# tia.net
KiCad netlist of a schematic drawn in Altium Designer
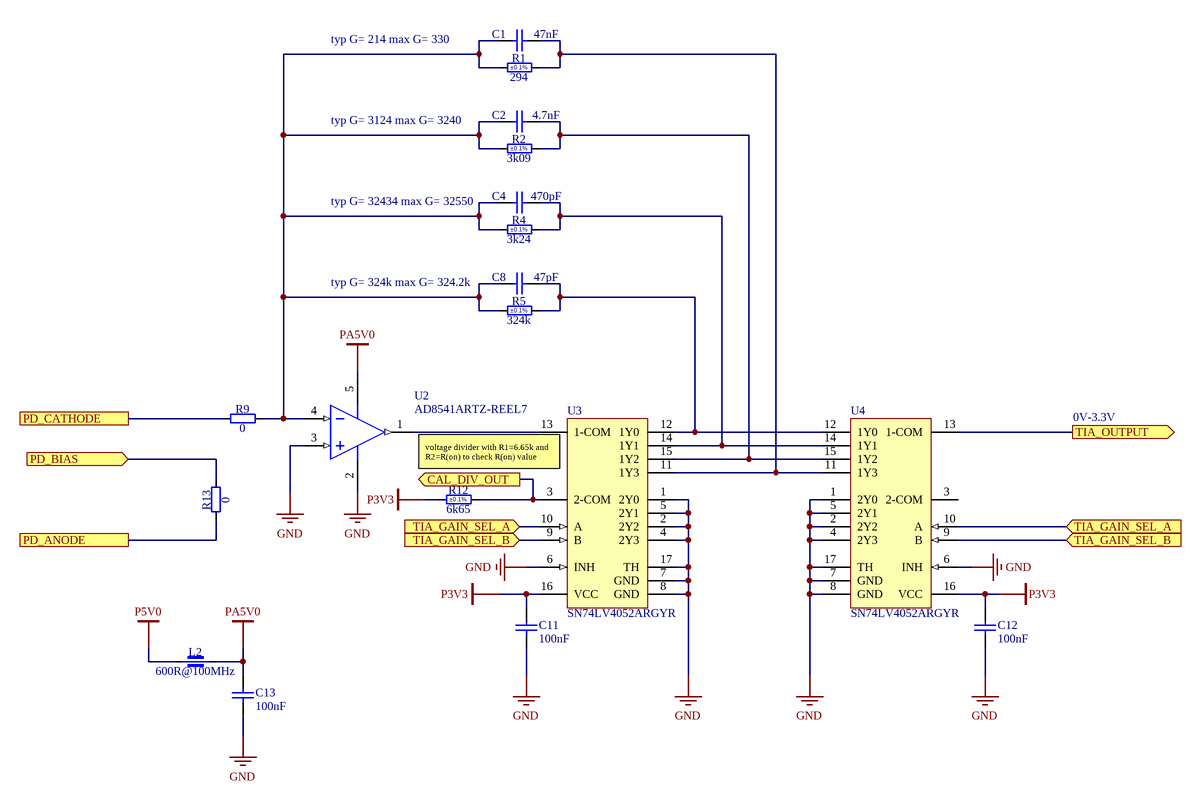
[diagram p0: tia.SchDoc]

(export (version "E")
  (design (tool "Eeschema 10.0.6"))
  (components
    (comp (ref "C1")
      (value "47nF")
      (footprint "CAPC1005X55N")
      (description "Non-polarised capacitor")
      (fields
        (field (name "PART NUMBER") "CC0402_47NF_16V_10%_X7R")
        (field (name "VOLTAGE") "16V")
        (field (name "AUTHOR") "CERN DEM JLC")
      )
      (libsource (lib "Capacitors") (part "Capacitor - non polarized"))
    )
    (comp (ref "C2")
      (value "4.7nF")
      (footprint "CAPC1005X55N")
      (description "Non-polarised capacitor")
      (fields
        (field (name "PART NUMBER") "CC0402_4.7NF_16V_10%_X7R")
        (field (name "VOLTAGE") "16V")
        (field (name "AUTHOR") "CERN DEM JLC")
      )
      (libsource (lib "Capacitors") (part "Capacitor - non polarized"))
    )
    (comp (ref "C4")
      (value "470pF")
      (footprint "CAPC1005X55N")
      (description "Non-polarised capacitor")
      (fields
        (field (name "PART NUMBER") "CC0402_470PF_50V_10%_X7R")
        (field (name "VOLTAGE") "50V")
        (field (name "AUTHOR") "CERN DEM JLC")
      )
      (libsource (lib "Capacitors") (part "Capacitor - non polarized"))
    )
    (comp (ref "C8")
      (value "47pF")
      (footprint "CAPC1005X55N")
      (description "Non-polarised capacitor")
      (fields
        (field (name "PART NUMBER") "CC0402_47PF_50V_5%_C0G")
        (field (name "VOLTAGE") "50V")
        (field (name "AUTHOR") "CERN DEM JLC")
      )
      (libsource (lib "Capacitors") (part "Capacitor - non polarized"))
    )
    (comp (ref "C11")
      (value "100nF")
      (footprint "CAPC1005X55N")
      (description "Non-polarised capacitor")
      (fields
        (field (name "TOLERANCE") "±10%")
        (field (name "VOLTAGE") "16V")
        (field (name "AUTHOR") "CERN DEM JLC")
      )
      (libsource (lib "Capacitors") (part "Capacitor - non polarized"))
    )
    (comp (ref "C12")
      (value "100nF")
      (footprint "CAPC1005X55N")
      (description "Non-polarised capacitor")
      (fields
        (field (name "TOLERANCE") "±10%")
        (field (name "VOLTAGE") "16V")
        (field (name "AUTHOR") "CERN DEM JLC")
      )
      (libsource (lib "Capacitors") (part "Capacitor - non polarized"))
    )
    (comp (ref "C13")
      (value "100nF")
      (footprint "CAPC1005X55N")
      (description "Non-polarised capacitor")
      (fields
        (field (name "TOLERANCE") "±10%")
        (field (name "VOLTAGE") "16V")
        (field (name "AUTHOR") "CERN DEM JLC")
      )
      (libsource (lib "Capacitors") (part "Capacitor - non polarized"))
    )
    (comp (ref "L2")
      (value "600R@100MHz")
      (footprint "INDC1005X55N")
      (fields
        (field (name "PART NUMBER") "IND0402_MURATA_BLM15HD601SN1")
        (field (name "POWER") "300mA")
        (field (name "TOLERANCE") "±25%")
        (field (name "AUTHOR") "CERN DEM JLC")
      )
      (libsource (lib "Inductors & Transformers") (part "Ferrite Bead"))
    )
    (comp (ref "R1")
      (value "294")
      (footprint "RESC1005X40N")
      (description "Resistor - 1%")
      (fields
        (field (name "TOLERANCE") "±0.1%")
        (field (name "PART NUMBER") "R0402_10K_1%_0.0625W_100PPM")
        (field (name "POWER") "0.0625W")
        (field (name "AUTHOR") "CERN DEM JLC")
      )
      (libsource (lib "Resistors") (part "Resistor - 1%"))
    )
    (comp (ref "R2")
      (value "3k09")
      (footprint "RESC1005X40N")
      (description "Resistor - 1%")
      (fields
        (field (name "TOLERANCE") "±0.1%")
        (field (name "PART NUMBER") "R0402_10K_1%_0.0625W_100PPM")
        (field (name "POWER") "0.0625W")
        (field (name "AUTHOR") "CERN DEM JLC")
      )
      (libsource (lib "Resistors") (part "Resistor - 1%"))
    )
    (comp (ref "R4")
      (value "3k24")
      (footprint "RESC1005X40N")
      (description "Resistor - 1%")
      (fields
        (field (name "TOLERANCE") "±0.1%")
        (field (name "PART NUMBER") "R0402_10K_1%_0.0625W_100PPM")
        (field (name "POWER") "0.0625W")
        (field (name "AUTHOR") "CERN DEM JLC")
      )
      (libsource (lib "Resistors") (part "Resistor - 1%"))
    )
    (comp (ref "R5")
      (value "324k")
      (footprint "RESC1005X40N")
      (description "Resistor - 1%")
      (fields
        (field (name "TOLERANCE") "±0.1%")
        (field (name "PART NUMBER") "R0402_10K_1%_0.0625W_100PPM")
        (field (name "POWER") "0.0625W")
        (field (name "AUTHOR") "CERN DEM JLC")
      )
      (libsource (lib "Resistors") (part "Resistor - 1%"))
    )
    (comp (ref "R9")
      (value "0")
      (footprint "RESC1005X40N")
      (description "Resistor")
      (fields
        (field (name "PART NUMBER") "R0402_0R_JUMPER")
        (field (name "MANUFACTURER") "GENERIC")
        (field (name "AUTHOR") "CERN DEM JLC")
      )
      (libsource (lib "Resistors") (part "Resistor"))
    )
    (comp (ref "R12")
      (value "6k65")
      (footprint "RESC1005X40N")
      (description "Resistor - 1%")
      (fields
        (field (name "TOLERANCE") "±0.1%")
        (field (name "PART NUMBER") "R0402_10K_1%_0.0625W_100PPM")
        (field (name "POWER") "0.0625W")
        (field (name "AUTHOR") "CERN DEM JLC")
      )
      (libsource (lib "Resistors") (part "Resistor - 1%"))
    )
    (comp (ref "R13")
      (value "0")
      (footprint "RESC1005X40N")
      (description "Resistor")
      (fields
        (field (name "PART NUMBER") "R0402_0R_JUMPER")
        (field (name "MANUFACTURER") "GENERIC")
        (field (name "AUTHOR") "CERN DEM JLC")
      )
      (libsource (lib "Resistors") (part "Resistor"))
    )
    (comp (ref "U2")
      (value "AD8541ARTZ-REEL7")
      (footprint "ADI-RJ-5_N")
      (fields (field (name "MANUFACTURER") "Analog Devices") (field (name "GENERIC PART NUMBER") "AD8541"))
      (libsource (lib "Altium Content Vault") (part "ADI-AD85XX-5"))
    )
    (comp (ref "U3")
      (value "SN74LV4052ARGYR")
      (footprint "FP-RGY0016A-MFG")
      (description "IC MULTIPLEXER DUAL 4X1 16VQFN")
      (libsource (lib "DiPho") (part "SN74LV4052ARGYR"))
    )
    (comp (ref "U4")
      (value "SN74LV4052ARGYR")
      (footprint "FP-RGY0016A-MFG")
      (description "IC MULTIPLEXER DUAL 4X1 16VQFN")
      (libsource (lib "") (part "SN74LV4052ARGYR_1"))
    )
  )
  (nets
    (net (code "1") (name "/CAL_DIV_OUT") (class "Default")
      (node (ref "R12") (pin "2") (pinfunction "2_2") (pintype "passive"))
      (node (ref "U3") (pin "3") (pinfunction "2-COM_3") (pintype "passive"))
    )
    (net (code "2") (name "/PD_ANODE") (class "Default")
      (node (ref "R13") (pin "1") (pinfunction "1_1") (pintype "passive"))
    )
    (net (code "3") (name "/PD_BIAS") (class "Default")
      (node (ref "R13") (pin "2") (pinfunction "2_2") (pintype "passive"))
    )
    (net (code "4") (name "/PD_CATHODE") (class "Default")
      (node (ref "R9") (pin "1") (pinfunction "1_1") (pintype "passive"))
    )
    (net (code "5") (name "/TIA_GAIN_SEL_A") (class "Default")
      (node (ref "U3") (pin "10") (pinfunction "A_10") (pintype "input"))
      (node (ref "U4") (pin "10") (pinfunction "A_10") (pintype "input"))
    )
    (net (code "6") (name "/TIA_GAIN_SEL_B") (class "Default")
      (node (ref "U3") (pin "9") (pinfunction "B_9") (pintype "input"))
      (node (ref "U4") (pin "9") (pinfunction "B_9") (pintype "input"))
    )
    (net (code "7") (name "/TIA_OUTPUT") (class "Default")
      (node (ref "U4") (pin "13") (pinfunction "1-COM_13") (pintype "passive"))
    )
    (net (code "8") (name "GND") (class "Default")
      (node (ref "C11") (pin "1") (pinfunction "1_1") (pintype "passive"))
      (node (ref "C12") (pin "1") (pinfunction "1_1") (pintype "passive"))
      (node (ref "C13") (pin "1") (pinfunction "1_1") (pintype "passive"))
      (node (ref "U2") (pin "2") (pinfunction "-V_2") (pintype "power_in"))
      (node (ref "U2") (pin "3") (pinfunction "+IN_A_3") (pintype "input"))
      (node (ref "U3") (pin "1") (pinfunction "2Y0_1") (pintype "passive"))
      (node (ref "U3") (pin "17") (pinfunction "TH_17") (pintype "power_in"))
      (node (ref "U3") (pin "2") (pinfunction "2Y2_2") (pintype "passive"))
      (node (ref "U3") (pin "4") (pinfunction "2Y3_4") (pintype "passive"))
      (node (ref "U3") (pin "5") (pinfunction "2Y1_5") (pintype "passive"))
      (node (ref "U3") (pin "6") (pinfunction "INH_6") (pintype "input"))
      (node (ref "U3") (pin "7") (pinfunction "GND_7") (pintype "power_in"))
      (node (ref "U3") (pin "8") (pinfunction "GND_8") (pintype "power_in"))
      (node (ref "U4") (pin "1") (pinfunction "2Y0_1") (pintype "passive"))
      (node (ref "U4") (pin "17") (pinfunction "TH_17") (pintype "power_in"))
      (node (ref "U4") (pin "2") (pinfunction "2Y2_2") (pintype "passive"))
      (node (ref "U4") (pin "4") (pinfunction "2Y3_4") (pintype "passive"))
      (node (ref "U4") (pin "5") (pinfunction "2Y1_5") (pintype "passive"))
      (node (ref "U4") (pin "6") (pinfunction "INH_6") (pintype "input"))
      (node (ref "U4") (pin "7") (pinfunction "GND_7") (pintype "power_in"))
      (node (ref "U4") (pin "8") (pinfunction "GND_8") (pintype "power_in"))
    )
    (net (code "9") (name "Net-(U2--IN_A)") (class "Default")
      (node (ref "C1") (pin "1") (pinfunction "1_1") (pintype "passive"))
      (node (ref "C2") (pin "1") (pinfunction "1_1") (pintype "passive"))
      (node (ref "C4") (pin "1") (pinfunction "1_1") (pintype "passive"))
      (node (ref "C8") (pin "1") (pinfunction "1_1") (pintype "passive"))
      (node (ref "R1") (pin "1") (pinfunction "1_1") (pintype "passive"))
      (node (ref "R2") (pin "1") (pinfunction "1_1") (pintype "passive"))
      (node (ref "R4") (pin "1") (pinfunction "1_1") (pintype "passive"))
      (node (ref "R5") (pin "1") (pinfunction "1_1") (pintype "passive"))
      (node (ref "R9") (pin "2") (pinfunction "2_2") (pintype "passive"))
      (node (ref "U2") (pin "4") (pinfunction "-IN_A_4") (pintype "input"))
    )
    (net (code "10") (name "Net-(U2-OUT_A)") (class "Default")
      (node (ref "U2") (pin "1") (pinfunction "OUT_A_1") (pintype "output"))
      (node (ref "U3") (pin "13") (pinfunction "1-COM_13") (pintype "passive"))
    )
    (net (code "11") (name "Net-(U3-1Y0)") (class "Default")
      (node (ref "C8") (pin "2") (pinfunction "2_2") (pintype "passive"))
      (node (ref "R5") (pin "2") (pinfunction "2_2") (pintype "passive"))
      (node (ref "U3") (pin "12") (pinfunction "1Y0_12") (pintype "passive"))
      (node (ref "U4") (pin "12") (pinfunction "1Y0_12") (pintype "passive"))
    )
    (net (code "12") (name "Net-(U3-1Y1)") (class "Default")
      (node (ref "C4") (pin "2") (pinfunction "2_2") (pintype "passive"))
      (node (ref "R4") (pin "2") (pinfunction "2_2") (pintype "passive"))
      (node (ref "U3") (pin "14") (pinfunction "1Y1_14") (pintype "passive"))
      (node (ref "U4") (pin "14") (pinfunction "1Y1_14") (pintype "passive"))
    )
    (net (code "13") (name "Net-(U3-1Y2)") (class "Default")
      (node (ref "C2") (pin "2") (pinfunction "2_2") (pintype "passive"))
      (node (ref "R2") (pin "2") (pinfunction "2_2") (pintype "passive"))
      (node (ref "U3") (pin "15") (pinfunction "1Y2_15") (pintype "passive"))
      (node (ref "U4") (pin "15") (pinfunction "1Y2_15") (pintype "passive"))
    )
    (net (code "14") (name "Net-(U3-1Y3)") (class "Default")
      (node (ref "C1") (pin "2") (pinfunction "2_2") (pintype "passive"))
      (node (ref "R1") (pin "2") (pinfunction "2_2") (pintype "passive"))
      (node (ref "U3") (pin "11") (pinfunction "1Y3_11") (pintype "passive"))
      (node (ref "U4") (pin "11") (pinfunction "1Y3_11") (pintype "passive"))
    )
    (net (code "15") (name "P3V3") (class "Default")
      (node (ref "C11") (pin "2") (pinfunction "2_2") (pintype "passive"))
      (node (ref "C12") (pin "2") (pinfunction "2_2") (pintype "passive"))
      (node (ref "R12") (pin "1") (pinfunction "1_1") (pintype "passive"))
      (node (ref "U3") (pin "16") (pinfunction "VCC_16") (pintype "power_in"))
      (node (ref "U4") (pin "16") (pinfunction "VCC_16") (pintype "power_in"))
    )
    (net (code "16") (name "P5V0") (class "Default")
      (node (ref "L2") (pin "1") (pinfunction "1_1") (pintype "passive"))
    )
    (net (code "17") (name "PA5V0") (class "Default")
      (node (ref "C13") (pin "2") (pinfunction "2_2") (pintype "passive"))
      (node (ref "L2") (pin "2") (pinfunction "2_2") (pintype "passive"))
      (node (ref "U2") (pin "5") (pinfunction "+V_5") (pintype "power_in"))
    )
    (net (code "18") (name "unconnected-(U4-2-COM-Pad3)") (class "Default")
      (node (ref "U4") (pin "3") (pinfunction "2-COM_3") (pintype "passive"))
    )
  )
)
